# NMEA-WiFi_Bridge_esp01_prod_thl_v3.net
KiCad netlist of a schematic drawn in EAGLE
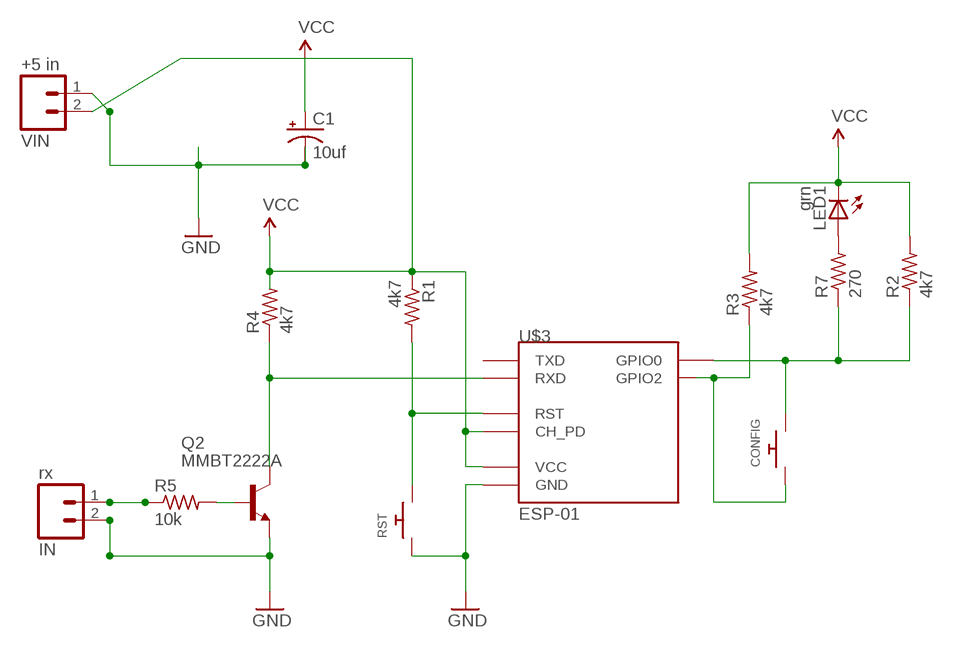
[diagram p0: schematic, sheet 1]

(export (version "E")
  (design (tool "Eeschema 10.0.6"))
  (components
    (comp (ref "C1")
      (value "10uf")
      (footprint "eagle-import:E2,5-6")
      (libsource (lib "eagle-import") (part "CPOL-USE2.5-6"))
    )
    (comp (ref "CONFIG")
      (value "SWITCH_PUSHBUTTONEVQ-PE")
      (footprint "eagle-import:TACT_PANA-EVQ")
      (libsource (lib "eagle-import") (part "SWITCH_PUSHBUTTONEVQ-PE"))
    )
    (comp (ref "IN")
      (value "rx")
      (footprint "eagle-import:MOLEX-1X2")
      (libsource (lib "eagle-import") (part "M02POLAR"))
    )
    (comp (ref "LED1")
      (value "grn")
      (footprint "eagle-import:LED3MM")
      (libsource (lib "eagle-import") (part "LED3MM"))
    )
    (comp (ref "Q2")
      (value "MMBT2222A")
      (footprint "eagle-import:TO92-CBE")
      (libsource (lib "eagle-import") (part "-NPN-TO92-CBEMPS2222A"))
    )
    (comp (ref "R1")
      (value "4k7")
      (footprint "eagle-import:0207_2V")
      (libsource (lib "eagle-import") (part "R-US_0207/2V"))
    )
    (comp (ref "R2")
      (value "4k7")
      (footprint "eagle-import:0207_7")
      (libsource (lib "eagle-import") (part "R-US_0207/7"))
    )
    (comp (ref "R3")
      (value "4k7")
      (footprint "eagle-import:0207_7")
      (libsource (lib "eagle-import") (part "R-US_0207/7"))
    )
    (comp (ref "R4")
      (value "4k7")
      (footprint "eagle-import:0207_5V")
      (libsource (lib "eagle-import") (part "R-US_0207/5V"))
    )
    (comp (ref "R5")
      (value "10k")
      (footprint "eagle-import:0207_2V")
      (libsource (lib "eagle-import") (part "rcl_R-US_0207/2V"))
    )
    (comp (ref "R7")
      (value "270")
      (footprint "eagle-import:0207_7")
      (libsource (lib "eagle-import") (part "R-US_0207/7"))
    )
    (comp (ref "RST")
      (value "SWITCH_PUSHBUTTONEVQ-PE")
      (footprint "eagle-import:TACT_PANA-EVQ")
      (libsource (lib "eagle-import") (part "SWITCH_PUSHBUTTONEVQ-PE"))
    )
    (comp (ref "U$3")
      (value "ESP-01")
      (footprint "eagle-import:ESP-01")
      (libsource (lib "eagle-import") (part "ESP-01"))
    )
    (comp (ref "VIN")
      (value "+5 in")
      (footprint "eagle-import:MOLEX-1X2")
      (libsource (lib "eagle-import") (part "M02POLAR"))
    )
  )
  (nets
    (net (code "1") (name "GND") (class "Default")
      (node (ref "C1") (pin "-") (pinfunction "-_-") (pintype "passive"))
      (node (ref "IN") (pin "2") (pinfunction "2_2") (pintype "passive"))
      (node (ref "Q2") (pin "E") (pinfunction "E_E") (pintype "passive"))
      (node (ref "RST") (pin "P$1") (pinfunction "P$1_P$1") (pintype "passive"))
      (node (ref "U$3") (pin "GND") (pinfunction "GND_GND") (pintype "bidirectional"))
      (node (ref "VIN") (pin "1") (pinfunction "1_1") (pintype "passive"))
    )
    (net (code "2") (name "Net-(CONFIG-PadP$1)") (class "Default")
      (node (ref "CONFIG") (pin "P$1") (pinfunction "P$1_P$1") (pintype "passive"))
      (node (ref "R3") (pin "1") (pinfunction "1_1") (pintype "passive"))
      (node (ref "U$3") (pin "GPIO2") (pinfunction "GPIO2_GPIO2") (pintype "bidirectional"))
    )
    (net (code "3") (name "Net-(CONFIG-PadP$2)") (class "Default")
      (node (ref "CONFIG") (pin "P$2") (pinfunction "P$2_P$2") (pintype "passive"))
      (node (ref "R2") (pin "1") (pinfunction "1_1") (pintype "passive"))
      (node (ref "R7") (pin "1") (pinfunction "1_1") (pintype "passive"))
      (node (ref "U$3") (pin "GPIO0") (pinfunction "GPIO0_GPIO0") (pintype "bidirectional"))
    )
    (net (code "4") (name "Net-(IN-Pad1)") (class "Default")
      (node (ref "IN") (pin "1") (pinfunction "1_1") (pintype "passive"))
      (node (ref "R5") (pin "1") (pinfunction "1_1") (pintype "passive"))
    )
    (net (code "5") (name "Net-(LED1-PadA)") (class "Default")
      (node (ref "LED1") (pin "A") (pinfunction "A_A") (pintype "passive"))
      (node (ref "R7") (pin "2") (pinfunction "2_2") (pintype "passive"))
    )
    (net (code "6") (name "Net-(Q2-PadB)") (class "Default")
      (node (ref "Q2") (pin "B") (pinfunction "B_B") (pintype "passive"))
      (node (ref "R5") (pin "2") (pinfunction "2_2") (pintype "passive"))
    )
    (net (code "7") (name "Net-(R1-Pad2)") (class "Default")
      (node (ref "R1") (pin "2") (pinfunction "2_2") (pintype "passive"))
      (node (ref "RST") (pin "P$2") (pinfunction "P$2_P$2") (pintype "passive"))
      (node (ref "U$3") (pin "RST") (pinfunction "RST_RST") (pintype "bidirectional"))
    )
    (net (code "8") (name "Net-(U$3-RXD)") (class "Default")
      (node (ref "Q2") (pin "C") (pinfunction "C_C") (pintype "passive"))
      (node (ref "R4") (pin "1") (pinfunction "1_1") (pintype "passive"))
      (node (ref "U$3") (pin "RX") (pinfunction "RXD_RX") (pintype "bidirectional"))
    )
    (net (code "9") (name "VCC") (class "Default")
      (node (ref "C1") (pin "+") (pinfunction "+_+") (pintype "passive"))
      (node (ref "LED1") (pin "K") (pinfunction "C_K") (pintype "passive"))
      (node (ref "R1") (pin "1") (pinfunction "1_1") (pintype "passive"))
      (node (ref "R2") (pin "2") (pinfunction "2_2") (pintype "passive"))
      (node (ref "R3") (pin "2") (pinfunction "2_2") (pintype "passive"))
      (node (ref "R4") (pin "2") (pinfunction "2_2") (pintype "passive"))
      (node (ref "U$3") (pin "CH_PD") (pinfunction "CH_PD_CH_PD") (pintype "bidirectional"))
      (node (ref "U$3") (pin "VCC") (pinfunction "VCC_VCC") (pintype "bidirectional"))
      (node (ref "VIN") (pin "2") (pinfunction "2_2") (pintype "passive"))
    )
    (net (code "10") (name "unconnected-(U$3-TXD-PadTX)") (class "Default")
      (node (ref "U$3") (pin "TX") (pinfunction "TXD_TX") (pintype "bidirectional"))
    )
  )
)
